# Buzzer.net
KiCad netlist of a schematic drawn in Altium Designer
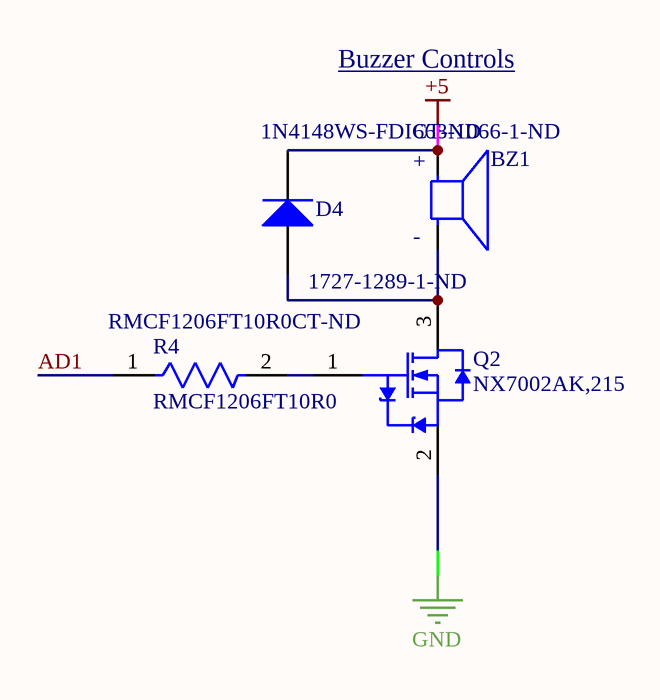
[diagram p0: Buzzer.SchDoc]

(export (version "E")
  (design (tool "Eeschema 10.0.6"))
  (components
    (comp (ref "BZ1")
      (value "SMT-0823-S-R")
      (footprint "XDCR_SMT-0823-S-R")
      (fields
        (field (name "MF") "PUI Audio")
        (field (name "MANUFACTURER") "Projects Unlimited")
        (field (name "SUPPLIER PART NUMBER 1") "668-1066-1-ND")
      )
      (libsource (lib "SMT-0823-S-R") (part "SMT-0823-S-R"))
    )
    (comp (ref "D4")
      (value "1N4148WS-7-F")
      (footprint "DIOD-SOD323-2-A_V")
      (description "Rectifier Diode, 1 Phase, 1 Element, 0.15A, 75V V(RRM), Silicon")
      (fields
        (field (name "SUPPLIER PART NUMBER 1") "1N4148WS-FDICT-ND")
        (field (name "MANUFACTURER") "Diodes")
      )
      (libsource (lib "Altium Content Vault") (part "D-AK-2"))
    )
    (comp (ref "Q2")
      (value "NX7002AK,215")
      (footprint "NXP-SOT23_L")
      (description "Single N-Channel Trench MOSFET, 60 V, -55 to 150 degC, 3-Pin SOT23, Tape and Reel")
      (fields
        (field (name "MANUFACTURER") "NXP Semiconductors")
        (field (name "SUPPLIER PART NUMBER 1") "1727-1289-1-ND")
      )
      (libsource (lib "Altium Content Vault") (part "NXP-NMOS-GSD-3"))
    )
    (comp (ref "R4")
      (value "RMCF1206FT10R0")
      (footprint "FP-RMCF1206-IPC_C")
      (description "RES 10 OHM 1% 1/4W 1206")
      (fields
        (field (name "TOLERANCE") "1%")
        (field (name "SUPPLIER PART NUMBER 1") "RMCF1206FT10R0CT-ND")
        (field (name "MANUFACTURER") "Stackpole Electronics")
      )
      (libsource (lib "Altium Content Vault") (part "1029c3af85768c4190bb7ad29bc67b5"))
    )
  )
  (nets
    (net (code "1") (name "+5") (class "Default")
      (node (ref "BZ1") (pin "P") (pinfunction "POS_P") (pintype "passive"))
      (node (ref "D4") (pin "2") (pinfunction "K_2") (pintype "passive"))
    )
    (net (code "2") (name "/AD1") (class "Default")
      (node (ref "R4") (pin "1") (pinfunction "1_1") (pintype "passive"))
    )
    (net (code "3") (name "GND") (class "Default")
      (node (ref "Q2") (pin "2") (pinfunction "S_2") (pintype "passive"))
    )
    (net (code "4") (name "Net-(BZ1-NEG)") (class "Default")
      (node (ref "BZ1") (pin "N") (pinfunction "NEG_N") (pintype "passive"))
      (node (ref "D4") (pin "1") (pinfunction "A_1") (pintype "passive"))
      (node (ref "Q2") (pin "3") (pinfunction "D_3") (pintype "passive"))
    )
    (net (code "5") (name "Net-(Q2-G)") (class "Default")
      (node (ref "Q2") (pin "1") (pinfunction "G_1") (pintype "passive"))
      (node (ref "R4") (pin "2") (pinfunction "2_2") (pintype "passive"))
    )
  )
)
